# QCopterRC_USB_Sch.net
KiCad netlist of a schematic drawn in Altium Designer
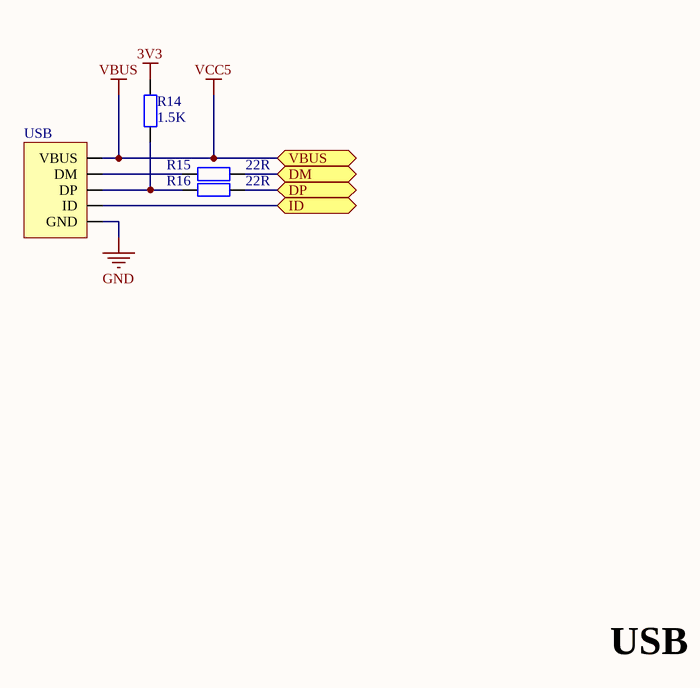
[diagram p0: QCopterRC_USB_Sch.SchDoc]

(export (version "E")
  (design (tool "Eeschema 10.0.6"))
  (components
    (comp (ref "R14")
      (value "1.5K")
      (footprint "PCB_Passive:RES_0603")
      (description "Resistor")
      (fields (field (name "Comment") "Res_0603"))
      (libsource (lib "SCH_Passive") (part "Res_0603"))
    )
    (comp (ref "R15")
      (value "22R")
      (footprint "PCB_Passive:RES_0603")
      (description "Resistor")
      (fields (field (name "Comment") "Res_0603"))
      (libsource (lib "") (part "Res_0603_1"))
    )
    (comp (ref "R16")
      (value "22R")
      (footprint "PCB_Passive:RES_0603")
      (description "Resistor")
      (fields (field (name "Comment") "Res_0603"))
      (libsource (lib "") (part "Res_0603_1"))
    )
    (comp (ref "USB")
      (value "USB_Micro")
      (footprint "PCB_USB:USB_MICRO_B")
      (description "USB")
      (libsource (lib "SCH_USB") (part "USB_Micro"))
    )
  )
  (nets
    (net (code "1") (name "/DM") (class "Default")
      (node (ref "R15") (pin "2") (pinfunction "2_2") (pintype "passive"))
    )
    (net (code "2") (name "/DP") (class "Default")
      (node (ref "R16") (pin "2") (pinfunction "2_2") (pintype "passive"))
    )
    (net (code "3") (name "/ID") (class "Default")
      (node (ref "USB") (pin "4") (pinfunction "ID_4") (pintype "passive"))
    )
    (net (code "4") (name "3V3") (class "Default")
      (node (ref "R14") (pin "2") (pinfunction "2_2") (pintype "passive"))
    )
    (net (code "5") (name "GND") (class "Default")
      (node (ref "USB") (pin "5") (pinfunction "GND_5") (pintype "passive"))
    )
    (net (code "6") (name "Net-(USB-DM)") (class "Default")
      (node (ref "R15") (pin "1") (pinfunction "1_1") (pintype "passive"))
      (node (ref "USB") (pin "2") (pinfunction "DM_2") (pintype "passive"))
    )
    (net (code "7") (name "Net-(USB-DP)") (class "Default")
      (node (ref "R14") (pin "1") (pinfunction "1_1") (pintype "passive"))
      (node (ref "R16") (pin "1") (pinfunction "1_1") (pintype "passive"))
      (node (ref "USB") (pin "3") (pinfunction "DP_3") (pintype "passive"))
    )
    (net (code "8") (name "VBUS") (class "Default")
      (node (ref "USB") (pin "1") (pinfunction "VBUS_1") (pintype "passive"))
    )
  )
)
